# thesis.net
KiCad netlist of a schematic drawn in EAGLE
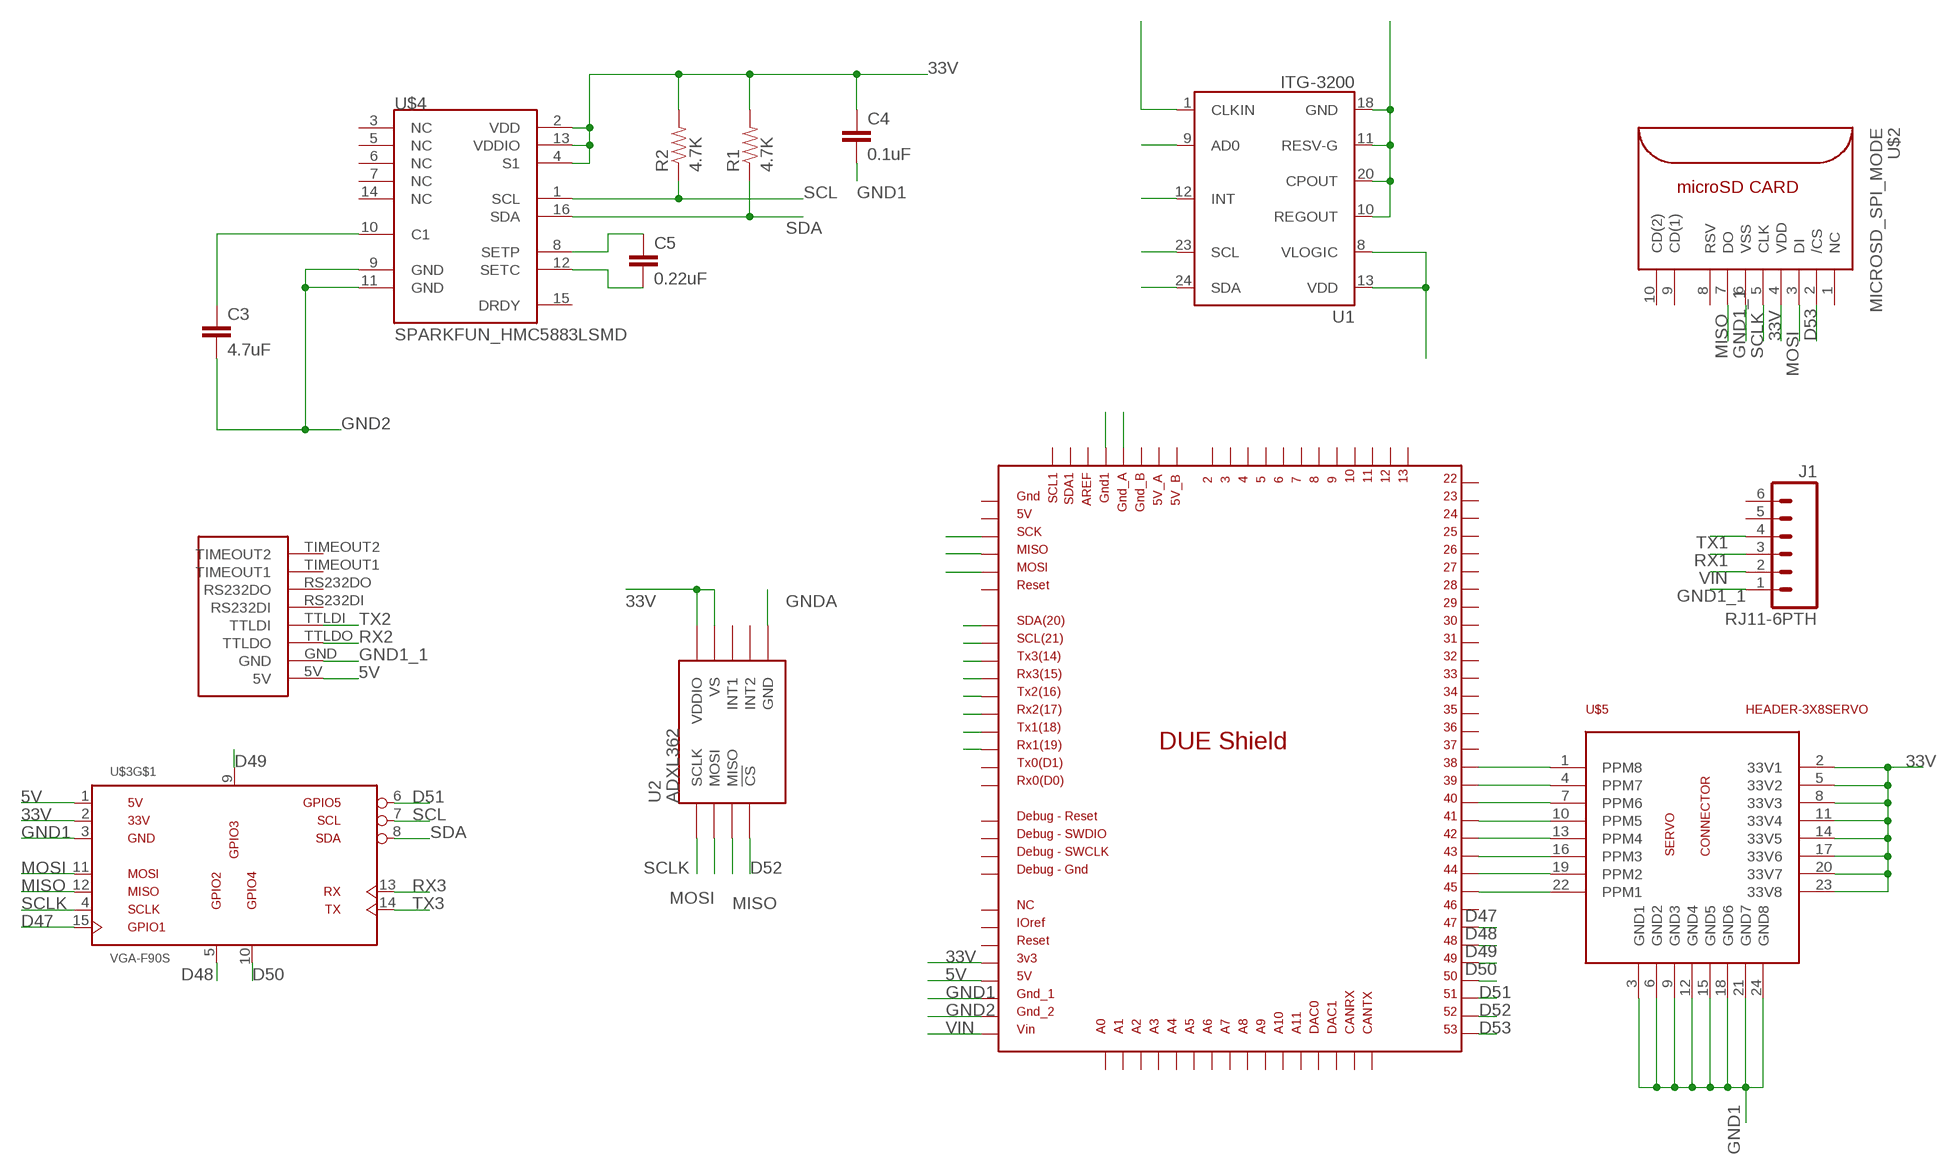
[diagram p0: schematic, sheet 1]

(export (version "E")
  (design (tool "Eeschema 10.0.6"))
  (components
    (comp (ref "C3")
      (value "4.7uF")
      (footprint "eagle-import:SPARKFUN_0402-CAP")
      (libsource (lib "eagle-import") (part "SPARKFUN_CAP0402-CAP"))
    )
    (comp (ref "C4")
      (value "0.1uF")
      (footprint "eagle-import:SPARKFUN_0402-CAP")
      (libsource (lib "eagle-import") (part "SPARKFUN_CAP0402-CAP"))
    )
    (comp (ref "C5")
      (value "0.22uF")
      (footprint "eagle-import:SPARKFUN_0402-CAP")
      (libsource (lib "eagle-import") (part "SPARKFUN_CAP0402-CAP"))
    )
    (comp (ref "J1")
      (value "RJ11-6PTH")
      (footprint "eagle-import:RJ11-6")
      (libsource (lib "eagle-import") (part "RJ11-6PTH"))
    )
    (comp (ref "R1")
      (value "4.7K")
      (footprint "eagle-import:SPARKFUN_0402-RES")
      (libsource (lib "eagle-import") (part "SPARKFUN_RESISTOR0402-RES"))
    )
    (comp (ref "R2")
      (value "4.7K")
      (footprint "eagle-import:SPARKFUN_0402-RES")
      (libsource (lib "eagle-import") (part "SPARKFUN_RESISTOR0402-RES"))
    )
    (comp (ref "U$1")
      (value "DUE(NORMAL)")
      (footprint "eagle-import:DUE(NORMAL)")
      (libsource (lib "eagle-import") (part "DUE(NORMAL)"))
    )
    (comp (ref "U$2")
      (value "MICROSD_SPI_MODE")
      (footprint "eagle-import:MICRO_SD_CONNECTOR")
      (libsource (lib "eagle-import") (part "MICROSD_SPI_MODE"))
    )
    (comp (ref "U$3")
      (value "VGA-F90S")
      (footprint "eagle-import:DB-15-F90+SHIELD-SMALL_PADS")
      (libsource (lib "eagle-import") (part "VGA-F90S"))
    )
    (comp (ref "U$4")
      (value "SPARKFUN_HMC5883LSMD")
      (footprint "eagle-import:SPARKFUN_16LPCC")
      (libsource (lib "eagle-import") (part "SPARKFUN_HMC5883LSMD"))
    )
    (comp (ref "U$5")
      (value "HEADER-3X8SERVO")
      (footprint "eagle-import:3X8RA")
      (libsource (lib "eagle-import") (part "HEADER-3X8SERVO"))
    )
    (comp (ref "U$6")
      (value "UBLOXLEA6TBOB")
      (footprint "eagle-import:UBLOXLEA6TBOB")
      (libsource (lib "eagle-import") (part "UBLOXLEA6TBOB"))
    )
    (comp (ref "U1")
      (value "ITG-3200")
      (footprint "eagle-import:QFN-24")
      (libsource (lib "eagle-import") (part "ITG-3200"))
    )
    (comp (ref "U2")
      (value "ADXL362")
      (footprint "eagle-import:ADXL362")
      (libsource (lib "eagle-import") (part "ADXL362"))
    )
  )
  (nets
    (net (code "1") (name "/5V") (class "Default")
      (node (ref "U$1") (pin "5V") (pinfunction "5V_5V") (pintype "bidirectional"))
      (node (ref "U$3") (pin "1") (pinfunction "VGA-R_1") (pintype "bidirectional"))
      (node (ref "U$6") (pin "5V") (pinfunction "5V_5V") (pintype "bidirectional"))
    )
    (net (code "2") (name "/33V") (class "Default")
      (node (ref "C4") (pin "1") (pinfunction "1_1") (pintype "passive"))
      (node (ref "R1") (pin "2") (pinfunction "2_2") (pintype "passive"))
      (node (ref "R2") (pin "2") (pinfunction "2_2") (pintype "passive"))
      (node (ref "U$1") (pin "3V3") (pinfunction "3V3_3V3") (pintype "bidirectional"))
      (node (ref "U$2") (pin "4") (pinfunction "VDD_4") (pintype "bidirectional"))
      (node (ref "U$3") (pin "2") (pinfunction "VGA-G_2") (pintype "bidirectional"))
      (node (ref "U$4") (pin "13") (pinfunction "VDDIO_13") (pintype "bidirectional"))
      (node (ref "U$4") (pin "2") (pinfunction "VDD_2") (pintype "bidirectional"))
      (node (ref "U$4") (pin "4") (pinfunction "S1_4") (pintype "bidirectional"))
      (node (ref "U$5") (pin "11") (pinfunction "33V4_11") (pintype "bidirectional"))
      (node (ref "U$5") (pin "14") (pinfunction "33V5_14") (pintype "bidirectional"))
      (node (ref "U$5") (pin "17") (pinfunction "33V6_17") (pintype "bidirectional"))
      (node (ref "U$5") (pin "2") (pinfunction "33V1_2") (pintype "bidirectional"))
      (node (ref "U$5") (pin "20") (pinfunction "33V7_20") (pintype "bidirectional"))
      (node (ref "U$5") (pin "23") (pinfunction "33V8_23") (pintype "bidirectional"))
      (node (ref "U$5") (pin "5") (pinfunction "33V2_5") (pintype "bidirectional"))
      (node (ref "U$5") (pin "8") (pinfunction "33V3_8") (pintype "bidirectional"))
      (node (ref "U1") (pin "13") (pinfunction "VDD_13") (pintype "bidirectional"))
      (node (ref "U1") (pin "8") (pinfunction "VLOGIC_8") (pintype "bidirectional"))
      (node (ref "U1") (pin "9") (pinfunction "AD0_9") (pintype "bidirectional"))
      (node (ref "U2") (pin "P$1") (pinfunction "VDDIO_P$1") (pintype "bidirectional"))
      (node (ref "U2") (pin "P$14") (pinfunction "VS_P$14") (pintype "bidirectional"))
    )
    (net (code "3") (name "/D47") (class "Default")
      (node (ref "U$1") (pin "47") (pinfunction "47_47") (pintype "bidirectional"))
      (node (ref "U$3") (pin "15") (pinfunction "ID3/SCL_15") (pintype "bidirectional"))
    )
    (net (code "4") (name "/D48") (class "Default")
      (node (ref "U$1") (pin "48") (pinfunction "48_48") (pintype "bidirectional"))
      (node (ref "U$3") (pin "5") (pinfunction "GND_5") (pintype "passive"))
    )
    (net (code "5") (name "/D49") (class "Default")
      (node (ref "U$1") (pin "49") (pinfunction "49_49") (pintype "bidirectional"))
      (node (ref "U$3") (pin "9") (pinfunction "+5V_9") (pintype "power_in"))
    )
    (net (code "6") (name "/D50") (class "Default")
      (node (ref "U$1") (pin "50") (pinfunction "50_50") (pintype "bidirectional"))
      (node (ref "U$3") (pin "10") (pinfunction "GND_10") (pintype "passive"))
    )
    (net (code "7") (name "/D51") (class "Default")
      (node (ref "U$1") (pin "51") (pinfunction "51_51") (pintype "bidirectional"))
      (node (ref "U$3") (pin "6") (pinfunction "VGA-R-_6") (pintype "passive"))
    )
    (net (code "8") (name "/D52") (class "Default")
      (node (ref "U$1") (pin "52") (pinfunction "52_52") (pintype "bidirectional"))
      (node (ref "U2") (pin "P$8") (pinfunction "~{CS}_P$8") (pintype "bidirectional"))
    )
    (net (code "9") (name "/D53") (class "Default")
      (node (ref "U$1") (pin "53") (pinfunction "53_53") (pintype "bidirectional"))
      (node (ref "U$2") (pin "2") (pinfunction "/CS_2") (pintype "bidirectional"))
    )
    (net (code "10") (name "/GND1") (class "Default")
      (node (ref "C4") (pin "2") (pinfunction "2_2") (pintype "passive"))
      (node (ref "U$1") (pin "GND_1") (pinfunction "GND_1_GND_1") (pintype "bidirectional"))
      (node (ref "U$3") (pin "3") (pinfunction "VGA-B_3") (pintype "bidirectional"))
      (node (ref "U$5") (pin "12") (pinfunction "GND4_12") (pintype "bidirectional"))
      (node (ref "U$5") (pin "15") (pinfunction "GND5_15") (pintype "bidirectional"))
      (node (ref "U$5") (pin "18") (pinfunction "GND6_18") (pintype "bidirectional"))
      (node (ref "U$5") (pin "21") (pinfunction "GND7_21") (pintype "bidirectional"))
      (node (ref "U$5") (pin "24") (pinfunction "GND8_24") (pintype "bidirectional"))
      (node (ref "U$5") (pin "3") (pinfunction "GND1_3") (pintype "bidirectional"))
      (node (ref "U$5") (pin "6") (pinfunction "GND2_6") (pintype "bidirectional"))
      (node (ref "U$5") (pin "9") (pinfunction "GND3_9") (pintype "bidirectional"))
    )
    (net (code "11") (name "/GND1_1") (class "Default")
      (node (ref "J1") (pin "1") (pinfunction "1_1") (pintype "passive"))
      (node (ref "U$1") (pin "GND1") (pinfunction "GND1_GND1") (pintype "bidirectional"))
      (node (ref "U$2") (pin "6") (pinfunction "VSS_6") (pintype "bidirectional"))
      (node (ref "U$6") (pin "GND") (pinfunction "GND_GND") (pintype "bidirectional"))
    )
    (net (code "12") (name "/GND2") (class "Default")
      (node (ref "C3") (pin "2") (pinfunction "2_2") (pintype "passive"))
      (node (ref "U$1") (pin "GND_2") (pinfunction "GND_2_GND_2") (pintype "bidirectional"))
      (node (ref "U$4") (pin "11") (pinfunction "GND_11") (pintype "bidirectional"))
      (node (ref "U$4") (pin "9") (pinfunction "GND_9") (pintype "bidirectional"))
    )
    (net (code "13") (name "/GNDA") (class "Default")
      (node (ref "U$1") (pin "GND_A") (pinfunction "GND_A_GND_A") (pintype "bidirectional"))
      (node (ref "U1") (pin "1") (pinfunction "CLKIN_1") (pintype "bidirectional"))
      (node (ref "U1") (pin "10") (pinfunction "REGOUT_10") (pintype "bidirectional"))
      (node (ref "U1") (pin "11") (pinfunction "RESV-G_11") (pintype "bidirectional"))
      (node (ref "U1") (pin "12") (pinfunction "INT_12") (pintype "bidirectional"))
      (node (ref "U1") (pin "18") (pinfunction "GND_18") (pintype "bidirectional"))
      (node (ref "U1") (pin "20") (pinfunction "CPOUT_20") (pintype "bidirectional"))
      (node (ref "U2") (pin "P$12") (pinfunction "GND_P$12") (pintype "bidirectional"))
      (node (ref "U2") (pin "P$13") (pinfunction "GND_P$13") (pintype "bidirectional"))
      (node (ref "U2") (pin "P$16") (pinfunction "GND_P$16") (pintype "bidirectional"))
    )
    (net (code "14") (name "/MISO") (class "Default")
      (node (ref "U$1") (pin "MISO_ICSP") (pinfunction "MISO_ICSP_MISO_ICSP") (pintype "bidirectional"))
      (node (ref "U$2") (pin "7") (pinfunction "DO_7") (pintype "bidirectional"))
      (node (ref "U$3") (pin "12") (pinfunction "ID1/SDA_12") (pintype "bidirectional"))
      (node (ref "U2") (pin "P$7") (pinfunction "MISO_P$7") (pintype "bidirectional"))
    )
    (net (code "15") (name "/MOSI") (class "Default")
      (node (ref "U$1") (pin "MOSI_ICSP") (pinfunction "MOSI_ICSP_MOSI_ICSP") (pintype "bidirectional"))
      (node (ref "U$2") (pin "3") (pinfunction "DI_3") (pintype "bidirectional"))
      (node (ref "U$3") (pin "11") (pinfunction "ID0/RES_11") (pintype "passive"))
      (node (ref "U2") (pin "P$6") (pinfunction "MOSI_P$6") (pintype "bidirectional"))
    )
    (net (code "16") (name "/RX1") (class "Default")
      (node (ref "J1") (pin "3") (pinfunction "3_3") (pintype "passive"))
      (node (ref "U$1") (pin "RX1") (pinfunction "RX1_RX1") (pintype "bidirectional"))
    )
    (net (code "17") (name "/RX2") (class "Default")
      (node (ref "U$1") (pin "RX2") (pinfunction "RX2_RX2") (pintype "bidirectional"))
      (node (ref "U$6") (pin "TTLDO") (pinfunction "TTLDO_TTLDO") (pintype "bidirectional"))
    )
    (net (code "18") (name "/RX3") (class "Default")
      (node (ref "U$1") (pin "RX3") (pinfunction "RX3_RX3") (pintype "bidirectional"))
      (node (ref "U$3") (pin "13") (pinfunction "VGA-HSYNC_13") (pintype "bidirectional"))
    )
    (net (code "19") (name "/SCL") (class "Default")
      (node (ref "R2") (pin "1") (pinfunction "1_1") (pintype "passive"))
      (node (ref "U$1") (pin "SCL") (pinfunction "SCL_SCL") (pintype "bidirectional"))
      (node (ref "U$3") (pin "7") (pinfunction "VGA-G-_7") (pintype "passive"))
      (node (ref "U$4") (pin "1") (pinfunction "SCL_1") (pintype "bidirectional"))
      (node (ref "U1") (pin "23") (pinfunction "SCL_23") (pintype "bidirectional"))
    )
    (net (code "20") (name "/SCLK") (class "Default")
      (node (ref "U$1") (pin "SCK_ICSP") (pinfunction "SCK_ICSP_SCK_ICSP") (pintype "bidirectional"))
      (node (ref "U$2") (pin "5") (pinfunction "CLK_5") (pintype "bidirectional"))
      (node (ref "U$3") (pin "4") (pinfunction "ID2/RES_4") (pintype "passive"))
      (node (ref "U2") (pin "P$4") (pinfunction "SCLK_P$4") (pintype "bidirectional"))
    )
    (net (code "21") (name "/SDA") (class "Default")
      (node (ref "R1") (pin "1") (pinfunction "1_1") (pintype "passive"))
      (node (ref "U$1") (pin "SDA") (pinfunction "SDA_SDA") (pintype "bidirectional"))
      (node (ref "U$3") (pin "8") (pinfunction "VGA-B-_8") (pintype "passive"))
      (node (ref "U$4") (pin "16") (pinfunction "SDA_16") (pintype "bidirectional"))
      (node (ref "U1") (pin "24") (pinfunction "SDA_24") (pintype "bidirectional"))
    )
    (net (code "22") (name "/TX1") (class "Default")
      (node (ref "J1") (pin "4") (pinfunction "4_4") (pintype "passive"))
      (node (ref "U$1") (pin "TX1") (pinfunction "TX1_TX1") (pintype "bidirectional"))
    )
    (net (code "23") (name "/TX2") (class "Default")
      (node (ref "U$1") (pin "TX2") (pinfunction "TX2_TX2") (pintype "bidirectional"))
      (node (ref "U$6") (pin "TTLDI") (pinfunction "TTLDI_TTLDI") (pintype "bidirectional"))
    )
    (net (code "24") (name "/TX3") (class "Default")
      (node (ref "U$1") (pin "TX3") (pinfunction "TX3_TX3") (pintype "bidirectional"))
      (node (ref "U$3") (pin "14") (pinfunction "VGA-VSYNC_14") (pintype "bidirectional"))
    )
    (net (code "25") (name "/VIN") (class "Default")
      (node (ref "J1") (pin "2") (pinfunction "2_2") (pintype "passive"))
      (node (ref "U$1") (pin "VIN") (pinfunction "VIN_VIN") (pintype "bidirectional"))
    )
    (net (code "26") (name "Net-(U$4-C1)") (class "Default")
      (node (ref "C3") (pin "1") (pinfunction "1_1") (pintype "passive"))
      (node (ref "U$4") (pin "10") (pinfunction "C1_10") (pintype "bidirectional"))
    )
    (net (code "27") (name "Net-(U$4-SETC)") (class "Default")
      (node (ref "C5") (pin "2") (pinfunction "2_2") (pintype "passive"))
      (node (ref "U$4") (pin "12") (pinfunction "SETC_12") (pintype "bidirectional"))
    )
    (net (code "28") (name "Net-(U$4-SETP)") (class "Default")
      (node (ref "C5") (pin "1") (pinfunction "1_1") (pintype "passive"))
      (node (ref "U$4") (pin "8") (pinfunction "SETP_8") (pintype "bidirectional"))
    )
    (net (code "29") (name "Net-(U$5-PPM1)") (class "Default")
      (node (ref "U$1") (pin "45") (pinfunction "45_45") (pintype "bidirectional"))
      (node (ref "U$5") (pin "22") (pinfunction "PPM1_22") (pintype "bidirectional"))
    )
    (net (code "30") (name "Net-(U$5-PPM2)") (class "Default")
      (node (ref "U$1") (pin "44") (pinfunction "44_44") (pintype "bidirectional"))
      (node (ref "U$5") (pin "19") (pinfunction "PPM2_19") (pintype "bidirectional"))
    )
    (net (code "31") (name "Net-(U$5-PPM3)") (class "Default")
      (node (ref "U$1") (pin "43") (pinfunction "43_43") (pintype "bidirectional"))
      (node (ref "U$5") (pin "16") (pinfunction "PPM3_16") (pintype "bidirectional"))
    )
    (net (code "32") (name "Net-(U$5-PPM4)") (class "Default")
      (node (ref "U$1") (pin "42") (pinfunction "42_42") (pintype "bidirectional"))
      (node (ref "U$5") (pin "13") (pinfunction "PPM4_13") (pintype "bidirectional"))
    )
    (net (code "33") (name "Net-(U$5-PPM5)") (class "Default")
      (node (ref "U$1") (pin "41") (pinfunction "41_41") (pintype "bidirectional"))
      (node (ref "U$5") (pin "10") (pinfunction "PPM5_10") (pintype "bidirectional"))
    )
    (net (code "34") (name "Net-(U$5-PPM6)") (class "Default")
      (node (ref "U$1") (pin "40") (pinfunction "40_40") (pintype "bidirectional"))
      (node (ref "U$5") (pin "7") (pinfunction "PPM6_7") (pintype "bidirectional"))
    )
    (net (code "35") (name "Net-(U$5-PPM7)") (class "Default")
      (node (ref "U$1") (pin "39") (pinfunction "39_39") (pintype "bidirectional"))
      (node (ref "U$5") (pin "4") (pinfunction "PPM7_4") (pintype "bidirectional"))
    )
    (net (code "36") (name "Net-(U$5-PPM8)") (class "Default")
      (node (ref "U$1") (pin "38") (pinfunction "38_38") (pintype "bidirectional"))
      (node (ref "U$5") (pin "1") (pinfunction "PPM8_1") (pintype "bidirectional"))
    )
    (net (code "37") (name "unconnected-(J1-Pad5)") (class "Default")
      (node (ref "J1") (pin "5") (pinfunction "5_5") (pintype "passive"))
    )
    (net (code "38") (name "unconnected-(J1-Pad6)") (class "Default")
      (node (ref "J1") (pin "6") (pinfunction "6_6") (pintype "passive"))
    )
    (net (code "39") (name "unconnected-(U$1-Pad2)") (class "Default")
      (node (ref "U$1") (pin "2") (pinfunction "2_2") (pintype "bidirectional"))
    )
    (net (code "40") (name "unconnected-(U$1-Pad3)") (class "Default")
      (node (ref "U$1") (pin "3") (pinfunction "3_3") (pintype "bidirectional"))
    )
    (net (code "41") (name "unconnected-(U$1-Pad4)") (class "Default")
      (node (ref "U$1") (pin "4") (pinfunction "4_4") (pintype "bidirectional"))
    )
    (net (code "42") (name "unconnected-(U$1-Pad5)") (class "Default")
      (node (ref "U$1") (pin "5") (pinfunction "5_5") (pintype "bidirectional"))
    )
    (net (code "43") (name "unconnected-(U$1-Pad5V_A)") (class "Default")
      (node (ref "U$1") (pin "5V_A") (pinfunction "5V_A_5V_A") (pintype "bidirectional"))
    )
    (net (code "44") (name "unconnected-(U$1-Pad5V_B)") (class "Default")
      (node (ref "U$1") (pin "5V_B") (pinfunction "5V_B_5V_B") (pintype "bidirectional"))
    )
    (net (code "45") (name "unconnected-(U$1-Pad5V_ICSP)") (class "Default")
      (node (ref "U$1") (pin "5V_ICSP") (pinfunction "5V_ICSP_5V_ICSP") (pintype "bidirectional"))
    )
    (net (code "46") (name "unconnected-(U$1-Pad6)") (class "Default")
      (node (ref "U$1") (pin "6") (pinfunction "6_6") (pintype "bidirectional"))
    )
    (net (code "47") (name "unconnected-(U$1-Pad7)") (class "Default")
      (node (ref "U$1") (pin "7") (pinfunction "7_7") (pintype "bidirectional"))
    )
    (net (code "48") (name "unconnected-(U$1-Pad8)") (class "Default")
      (node (ref "U$1") (pin "8") (pinfunction "8_8") (pintype "bidirectional"))
    )
    (net (code "49") (name "unconnected-(U$1-Pad9)") (class "Default")
      (node (ref "U$1") (pin "9") (pinfunction "9_9") (pintype "bidirectional"))
    )
    (net (code "50") (name "unconnected-(U$1-Pad10)") (class "Default")
      (node (ref "U$1") (pin "10") (pinfunction "10_10") (pintype "bidirectional"))
    )
    (net (code "51") (name "unconnected-(U$1-Pad11)") (class "Default")
      (node (ref "U$1") (pin "11") (pinfunction "11_11") (pintype "bidirectional"))
    )
    (net (code "52") (name "unconnected-(U$1-Pad12)") (class "Default")
      (node (ref "U$1") (pin "12") (pinfunction "12_12") (pintype "bidirectional"))
    )
    (net (code "53") (name "unconnected-(U$1-Pad13)") (class "Default")
      (node (ref "U$1") (pin "13") (pinfunction "13_13") (pintype "bidirectional"))
    )
    (net (code "54") (name "unconnected-(U$1-Pad22)") (class "Default")
      (node (ref "U$1") (pin "22") (pinfunction "22_22") (pintype "bidirectional"))
    )
    (net (code "55") (name "unconnected-(U$1-Pad23)") (class "Default")
      (node (ref "U$1") (pin "23") (pinfunction "23_23") (pintype "bidirectional"))
    )
    (net (code "56") (name "unconnected-(U$1-Pad24)") (class "Default")
      (node (ref "U$1") (pin "24") (pinfunction "24_24") (pintype "bidirectional"))
    )
    (net (code "57") (name "unconnected-(U$1-Pad25)") (class "Default")
      (node (ref "U$1") (pin "25") (pinfunction "25_25") (pintype "bidirectional"))
    )
    (net (code "58") (name "unconnected-(U$1-Pad26)") (class "Default")
      (node (ref "U$1") (pin "26") (pinfunction "26_26") (pintype "bidirectional"))
    )
    (net (code "59") (name "unconnected-(U$1-Pad27)") (class "Default")
      (node (ref "U$1") (pin "27") (pinfunction "27_27") (pintype "bidirectional"))
    )
    (net (code "60") (name "unconnected-(U$1-Pad28)") (class "Default")
      (node (ref "U$1") (pin "28") (pinfunction "28_28") (pintype "bidirectional"))
    )
    (net (code "61") (name "unconnected-(U$1-Pad29)") (class "Default")
      (node (ref "U$1") (pin "29") (pinfunction "29_29") (pintype "bidirectional"))
    )
    (net (code "62") (name "unconnected-(U$1-Pad30)") (class "Default")
      (node (ref "U$1") (pin "30") (pinfunction "30_30") (pintype "bidirectional"))
    )
    (net (code "63") (name "unconnected-(U$1-Pad31)") (class "Default")
      (node (ref "U$1") (pin "31") (pinfunction "31_31") (pintype "bidirectional"))
    )
    (net (code "64") (name "unconnected-(U$1-Pad32)") (class "Default")
      (node (ref "U$1") (pin "32") (pinfunction "32_32") (pintype "bidirectional"))
    )
    (net (code "65") (name "unconnected-(U$1-Pad33)") (class "Default")
      (node (ref "U$1") (pin "33") (pinfunction "33_33") (pintype "bidirectional"))
    )
    (net (code "66") (name "unconnected-(U$1-Pad34)") (class "Default")
      (node (ref "U$1") (pin "34") (pinfunction "34_34") (pintype "bidirectional"))
    )
    (net (code "67") (name "unconnected-(U$1-Pad35)") (class "Default")
      (node (ref "U$1") (pin "35") (pinfunction "35_35") (pintype "bidirectional"))
    )
    (net (code "68") (name "unconnected-(U$1-Pad36)") (class "Default")
      (node (ref "U$1") (pin "36") (pinfunction "36_36") (pintype "bidirectional"))
    )
    (net (code "69") (name "unconnected-(U$1-Pad37)") (class "Default")
      (node (ref "U$1") (pin "37") (pinfunction "37_37") (pintype "bidirectional"))
    )
    (net (code "70") (name "unconnected-(U$1-Pad46)") (class "Default")
      (node (ref "U$1") (pin "46") (pinfunction "46_46") (pintype "bidirectional"))
    )
    (net (code "71") (name "unconnected-(U$1-PadA0)") (class "Default")
      (node (ref "U$1") (pin "A0") (pinfunction "A0_A0") (pintype "bidirectional"))
    )
    (net (code "72") (name "unconnected-(U$1-PadA1)") (class "Default")
      (node (ref "U$1") (pin "A1") (pinfunction "A1_A1") (pintype "bidirectional"))
    )
    (net (code "73") (name "unconnected-(U$1-PadA2)") (class "Default")
      (node (ref "U$1") (pin "A2") (pinfunction "A2_A2") (pintype "bidirectional"))
    )
    (net (code "74") (name "unconnected-(U$1-PadA3)") (class "Default")
      (node (ref "U$1") (pin "A3") (pinfunction "A3_A3") (pintype "bidirectional"))
    )
    (net (code "75") (name "unconnected-(U$1-PadA4)") (class "Default")
      (node (ref "U$1") (pin "A4") (pinfunction "A4_A4") (pintype "bidirectional"))
    )
    (net (code "76") (name "unconnected-(U$1-PadA5)") (class "Default")
      (node (ref "U$1") (pin "A5") (pinfunction "A5_A5") (pintype "bidirectional"))
    )
    (net (code "77") (name "unconnected-(U$1-PadA6)") (class "Default")
      (node (ref "U$1") (pin "A6") (pinfunction "A6_A6") (pintype "bidirectional"))
    )
    (net (code "78") (name "unconnected-(U$1-PadA7)") (class "Default")
      (node (ref "U$1") (pin "A7") (pinfunction "A7_A7") (pintype "bidirectional"))
    )
    (net (code "79") (name "unconnected-(U$1-PadA8)") (class "Default")
      (node (ref "U$1") (pin "A8") (pinfunction "A8_A8") (pintype "bidirectional"))
    )
    (net (code "80") (name "unconnected-(U$1-PadA9)") (class "Default")
      (node (ref "U$1") (pin "A9") (pinfunction "A9_A9") (pintype "bidirectional"))
    )
    (net (code "81") (name "unconnected-(U$1-PadA10)") (class "Default")
      (node (ref "U$1") (pin "A10") (pinfunction "A10_A10") (pintype "bidirectional"))
    )
    (net (code "82") (name "unconnected-(U$1-PadA11)") (class "Default")
      (node (ref "U$1") (pin "A11") (pinfunction "A11_A11") (pintype "bidirectional"))
    )
    (net (code "83") (name "unconnected-(U$1-PadAREF)") (class "Default")
      (node (ref "U$1") (pin "AREF") (pinfunction "AREF_AREF") (pintype "bidirectional"))
    )
    (net (code "84") (name "unconnected-(U$1-PadCANRX)") (class "Default")
      (node (ref "U$1") (pin "CANRX") (pinfunction "CANRX_CANRX") (pintype "bidirectional"))
    )
    (net (code "85") (name "unconnected-(U$1-PadCANTX)") (class "Default")
      (node (ref "U$1") (pin "CANTX") (pinfunction "CANTX_CANTX") (pintype "bidirectional"))
    )
    (net (code "86") (name "unconnected-(U$1-PadDAC0)") (class "Default")
      (node (ref "U$1") (pin "DAC0") (pinfunction "DAC0_DAC0") (pintype "bidirectional"))
    )
    (net (code "87") (name "unconnected-(U$1-PadDAC1)") (class "Default")
      (node (ref "U$1") (pin "DAC1") (pinfunction "DAC1_DAC1") (pintype "bidirectional"))
    )
    (net (code "88") (name "unconnected-(U$1-PadGND_B)") (class "Default")
      (node (ref "U$1") (pin "GND_B") (pinfunction "GND_B_GND_B") (pintype "bidirectional"))
    )
    (net (code "89") (name "unconnected-(U$1-PadGND_DEBUG)") (class "Default")
      (node (ref "U$1") (pin "GND_DEBUG") (pinfunction "GND_DEBUG_GND_DEBUG") (pintype "bidirectional"))
    )
    (net (code "90") (name "unconnected-(U$1-PadGND_ICSP)") (class "Default")
      (node (ref "U$1") (pin "GND_ICSP") (pinfunction "GND_ICSP_GND_ICSP") (pintype "bidirectional"))
    )
    (net (code "91") (name "unconnected-(U$1-PadIOREF)") (class "Default")
      (node (ref "U$1") (pin "IOREF") (pinfunction "IOREF_IOREF") (pintype "bidirectional"))
    )
    (net (code "92") (name "unconnected-(U$1-PadNC)") (class "Default")
      (node (ref "U$1") (pin "NC") (pinfunction "NC_NC") (pintype "bidirectional"))
    )
    (net (code "93") (name "unconnected-(U$1-PadRESET)") (class "Default")
      (node (ref "U$1") (pin "RESET") (pinfunction "RESET_RESET") (pintype "bidirectional"))
    )
    (net (code "94") (name "unconnected-(U$1-PadRESET_DEBUG)") (class "Default")
      (node (ref "U$1") (pin "RESET_DEBUG") (pinfunction "RESET_DEBUG_RESET_DEBUG") (pintype "bidirectional"))
    )
    (net (code "95") (name "unconnected-(U$1-PadRESET_ICSP)") (class "Default")
      (node (ref "U$1") (pin "RESET_ICSP") (pinfunction "RESET_ICSP_RESET_ICSP") (pintype "bidirectional"))
    )
    (net (code "96") (name "unconnected-(U$1-PadRX0)") (class "Default")
      (node (ref "U$1") (pin "RX0") (pinfunction "RX0_RX0") (pintype "bidirectional"))
    )
    (net (code "97") (name "unconnected-(U$1-PadSCL1)") (class "Default")
      (node (ref "U$1") (pin "SCL1") (pinfunction "SCL1_SCL1") (pintype "bidirectional"))
    )
    (net (code "98") (name "unconnected-(U$1-PadSDA1)") (class "Default")
      (node (ref "U$1") (pin "SDA1") (pinfunction "SDA1_SDA1") (pintype "bidirectional"))
    )
    (net (code "99") (name "unconnected-(U$1-PadSWCLK_DEBUG)") (class "Default")
      (node (ref "U$1") (pin "SWCLK_DEBUG") (pinfunction "SWCLK_DEBUG_SWCLK_DEBUG") (pintype "bidirectional"))
    )
    (net (code "100") (name "unconnected-(U$1-PadSWDIO_DEBUG)") (class "Default")
      (node (ref "U$1") (pin "SWDIO_DEBUG") (pinfunction "SWDIO_DEBUG_SWDIO_DEBUG") (pintype "bidirectional"))
    )
    (net (code "101") (name "unconnected-(U$1-PadTX0)") (class "Default")
      (node (ref "U$1") (pin "TX0") (pinfunction "TX0_TX0") (pintype "bidirectional"))
    )
    (net (code "102") (name "unconnected-(U$2-CD(1)-Pad9)") (class "Default")
      (node (ref "U$2") (pin "9") (pinfunction "CD(1)_9") (pintype "bidirectional"))
    )
    (net (code "103") (name "unconnected-(U$2-CD(2)-Pad10)") (class "Default")
      (node (ref "U$2") (pin "10") (pinfunction "CD(2)_10") (pintype "bidirectional"))
    )
    (net (code "104") (name "unconnected-(U$2-NC-Pad1)") (class "Default")
      (node (ref "U$2") (pin "1") (pinfunction "NC_1") (pintype "bidirectional"))
    )
    (net (code "105") (name "unconnected-(U$2-RSV-Pad8)") (class "Default")
      (node (ref "U$2") (pin "8") (pinfunction "RSV_8") (pintype "bidirectional"))
    )
    (net (code "106") (name "unconnected-(U$4-DRDY-Pad15)") (class "Default")
      (node (ref "U$4") (pin "15") (pinfunction "DRDY_15") (pintype "bidirectional"))
    )
    (net (code "107") (name "unconnected-(U$4-NC-Pad3)") (class "Default")
      (node (ref "U$4") (pin "3") (pinfunction "NC_3") (pintype "bidirectional"))
    )
    (net (code "108") (name "unconnected-(U$4-NC-Pad5)") (class "Default")
      (node (ref "U$4") (pin "5") (pinfunction "NC_5") (pintype "bidirectional"))
    )
    (net (code "109") (name "unconnected-(U$4-NC-Pad6)") (class "Default")
      (node (ref "U$4") (pin "6") (pinfunction "NC_6") (pintype "bidirectional"))
    )
    (net (code "110") (name "unconnected-(U$4-NC-Pad7)") (class "Default")
      (node (ref "U$4") (pin "7") (pinfunction "NC_7") (pintype "bidirectional"))
    )
    (net (code "111") (name "unconnected-(U$4-NC-Pad14)") (class "Default")
      (node (ref "U$4") (pin "14") (pinfunction "NC_14") (pintype "bidirectional"))
    )
    (net (code "112") (name "unconnected-(U$6-PadRS232DI)") (class "Default")
      (node (ref "U$6") (pin "RS232DI") (pinfunction "RS232DI_RS232DI") (pintype "bidirectional"))
    )
    (net (code "113") (name "unconnected-(U$6-PadRS232DO)") (class "Default")
      (node (ref "U$6") (pin "RS232DO") (pinfunction "RS232DO_RS232DO") (pintype "bidirectional"))
    )
    (net (code "114") (name "unconnected-(U$6-PadTIMEOUT1)") (class "Default")
      (node (ref "U$6") (pin "TIMEOUT1") (pinfunction "TIMEOUT1_TIMEOUT1") (pintype "bidirectional"))
    )
    (net (code "115") (name "unconnected-(U$6-PadTIMEOUT2)") (class "Default")
      (node (ref "U$6") (pin "TIMEOUT2") (pinfunction "TIMEOUT2_TIMEOUT2") (pintype "bidirectional"))
    )
    (net (code "116") (name "unconnected-(U2-INT1-PadP$11)") (class "Default")
      (node (ref "U2") (pin "P$11") (pinfunction "INT1_P$11") (pintype "bidirectional"))
    )
    (net (code "117") (name "unconnected-(U2-INT2-PadP$9)") (class "Default")
      (node (ref "U2") (pin "P$9") (pinfunction "INT2_P$9") (pintype "bidirectional"))
    )
  )
)
